# discrete_fan_controller.net
KiCad netlist of a schematic drawn in EAGLE
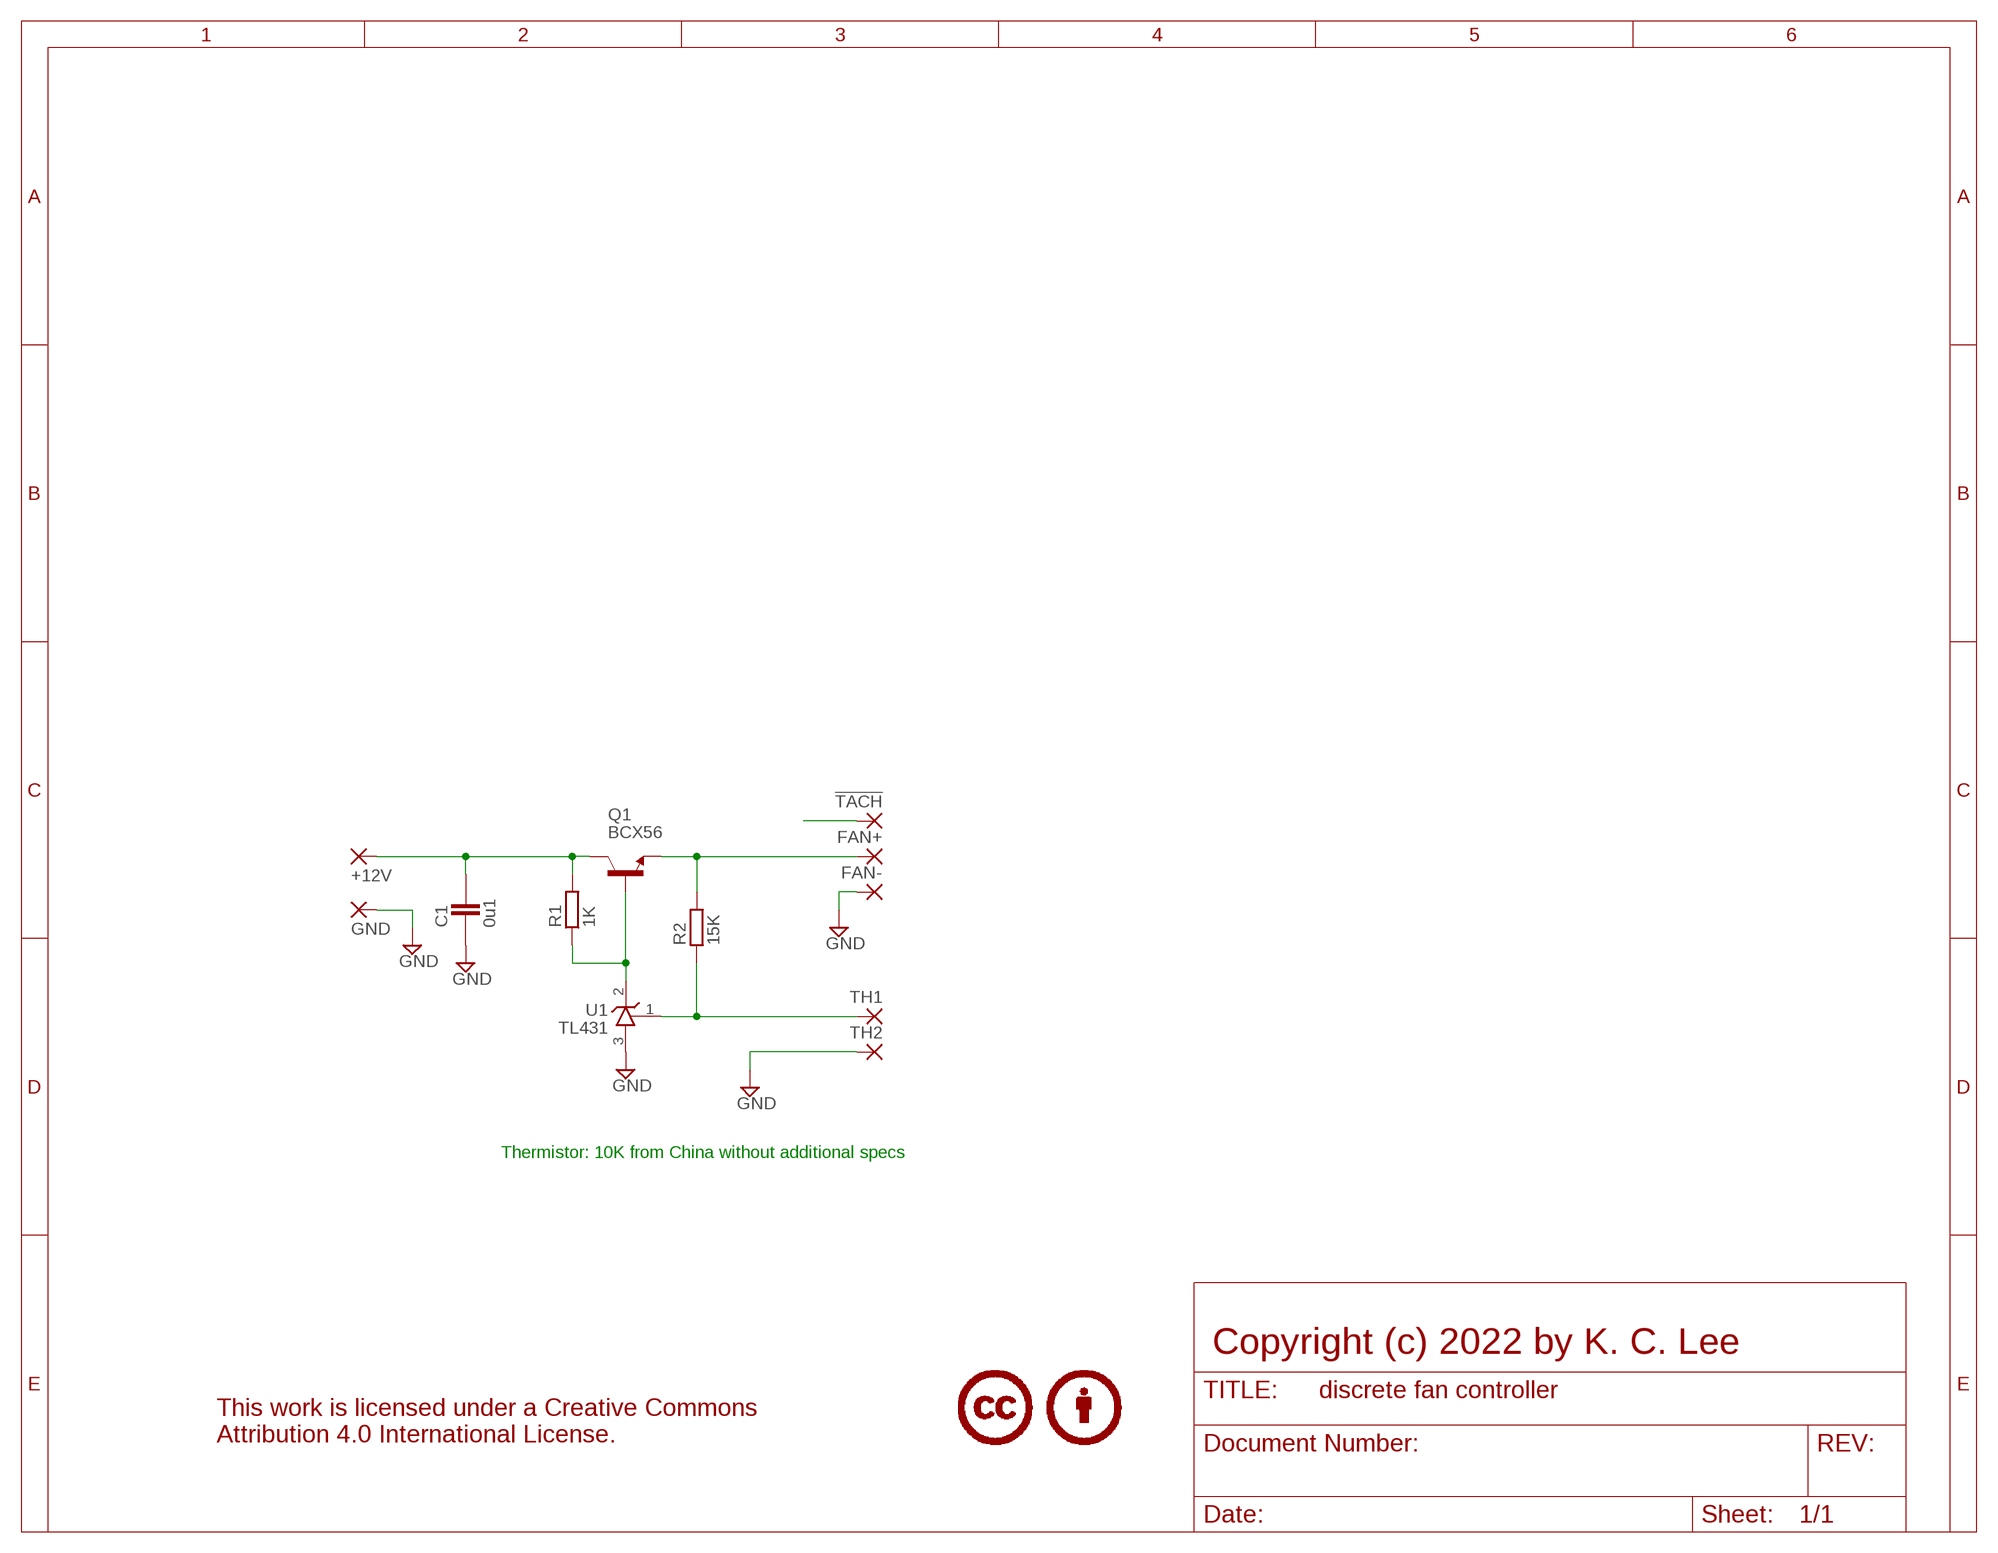
[diagram p0: schematic, sheet 1]

(export (version "E")
  (design (tool "Eeschema 10.0.6"))
  (components
    (comp (ref "!TACH")
      (value "SMD2")
      (footprint "eagle-import:SMD1,27-2,54")
      (libsource (lib "eagle-import") (part "SMD2"))
    )
    (comp (ref "+12V")
      (value "SMD2")
      (footprint "eagle-import:SMD1,27-2,54")
      (libsource (lib "eagle-import") (part "SMD2"))
    )
    (comp (ref "C1")
      (value "0u1")
      (footprint "eagle-import:CAPC2012X145AN")
      (libsource (lib "eagle-import") (part "CAPACITOR_0805"))
    )
    (comp (ref "FAN+")
      (value "SMD2")
      (footprint "eagle-import:SMD1,27-2,54")
      (libsource (lib "eagle-import") (part "SMD2"))
    )
    (comp (ref "FAN-")
      (value "SMD2")
      (footprint "eagle-import:SMD1,27-2,54")
      (libsource (lib "eagle-import") (part "SMD2"))
    )
    (comp (ref "GND")
      (value "SMD2")
      (footprint "eagle-import:SMD1,27-2,54")
      (libsource (lib "eagle-import") (part "SMD2"))
    )
    (comp (ref "LICENSE1")
      (value "CC-BY50%")
      (footprint "eagle-import:CC-BY-50")
      (libsource (lib "eagle-import") (part "CC-BY50%"))
    )
    (comp (ref "Q1")
      (value "BCX56")
      (footprint "eagle-import:SOT89")
      (libsource (lib "eagle-import") (part "NPN_SOT89SOT89"))
    )
    (comp (ref "R1")
      (value "1K")
      (footprint "eagle-import:RESC1608X55N")
      (libsource (lib "eagle-import") (part "RESISTOR_0603"))
    )
    (comp (ref "R2")
      (value "15K")
      (footprint "eagle-import:RESC1608X55N")
      (libsource (lib "eagle-import") (part "RESISTOR_0603"))
    )
    (comp (ref "TH1")
      (value "SMD2")
      (footprint "eagle-import:SMD1,27-2,54")
      (libsource (lib "eagle-import") (part "SMD2"))
    )
    (comp (ref "TH2")
      (value "SMD2")
      (footprint "eagle-import:SMD1,27-2,54")
      (libsource (lib "eagle-import") (part "SMD2"))
    )
    (comp (ref "U1")
      (value "TL431")
      (footprint "eagle-import:SOT95P280X135-3N")
      (libsource (lib "eagle-import") (part "TL_431DBZ"))
    )
  )
  (nets
    (net (code "1") (name "GND") (class "Default")
      (node (ref "C1") (pin "1") (pinfunction "1_1") (pintype "passive"))
      (node (ref "FAN-") (pin "1") (pinfunction "P_1") (pintype "passive"))
      (node (ref "GND") (pin "1") (pinfunction "P_1") (pintype "passive"))
      (node (ref "TH2") (pin "1") (pinfunction "P_1") (pintype "passive"))
      (node (ref "U1") (pin "3") (pinfunction "A_3") (pintype "passive"))
    )
    (net (code "2") (name "Net-(+12V-P)") (class "Default")
      (node (ref "+12V") (pin "1") (pinfunction "P_1") (pintype "passive"))
      (node (ref "C1") (pin "2") (pinfunction "2_2") (pintype "passive"))
      (node (ref "Q1") (pin "2") (pinfunction "C_2") (pintype "passive"))
      (node (ref "Q1") (pin "4") (pinfunction "C_4") (pintype "passive"))
      (node (ref "R1") (pin "2") (pinfunction "2_2") (pintype "passive"))
    )
    (net (code "3") (name "Net-(FAN+-P)") (class "Default")
      (node (ref "FAN+") (pin "1") (pinfunction "P_1") (pintype "passive"))
      (node (ref "Q1") (pin "3") (pinfunction "E_3") (pintype "passive"))
      (node (ref "R2") (pin "2") (pinfunction "2_2") (pintype "passive"))
    )
    (net (code "4") (name "Net-(Q1-B)") (class "Default")
      (node (ref "Q1") (pin "1") (pinfunction "B_1") (pintype "passive"))
      (node (ref "R1") (pin "1") (pinfunction "1_1") (pintype "passive"))
      (node (ref "U1") (pin "2") (pinfunction "C_2") (pintype "passive"))
    )
    (net (code "5") (name "Net-(TH1-P)") (class "Default")
      (node (ref "R2") (pin "1") (pinfunction "1_1") (pintype "passive"))
      (node (ref "TH1") (pin "1") (pinfunction "P_1") (pintype "passive"))
      (node (ref "U1") (pin "1") (pinfunction "R_1") (pintype "passive"))
    )
    (net (code "6") (name "unconnected-(!TACH-P-Pad1)") (class "Default")
      (node (ref "!TACH") (pin "1") (pinfunction "P_1") (pintype "passive"))
    )
  )
)
